# ProPrj_Solid_Cell__2026-03-29.net
KiCad netlist of a schematic drawn in EasyEDA Pro
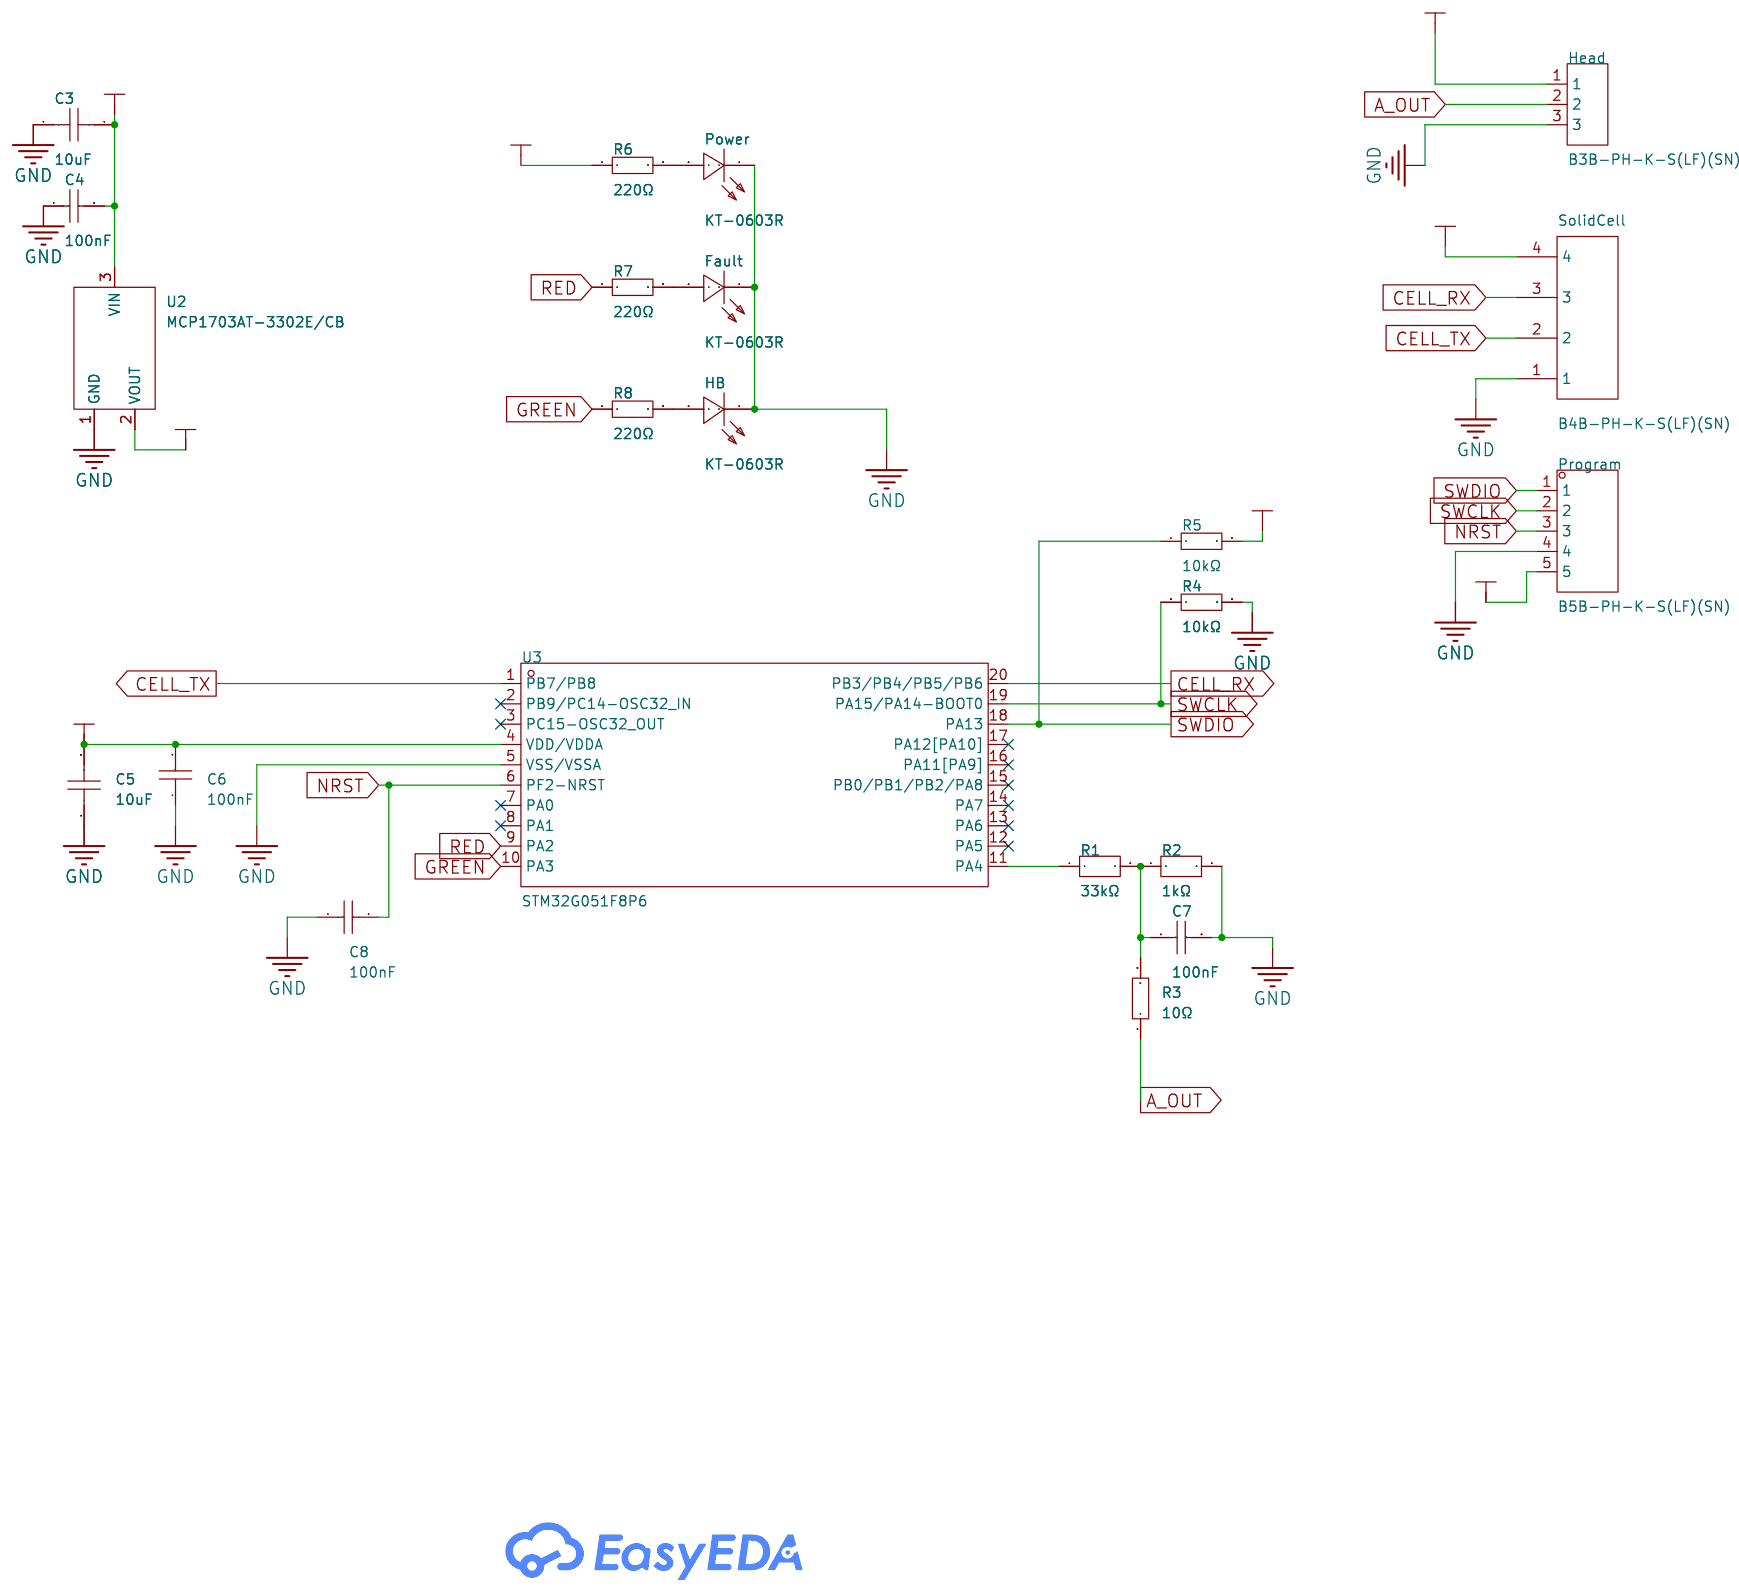
[diagram p0: schematic sheet]

(export (version "E")
  (design (tool "Eeschema 10.0.6"))
  (components
    (comp (ref "C3")
      (value "10uF")
      (footprint "easyedapro:C0603")
      (description "Capacitance:10uF Tolerance:±20% Tolerance:±20% Voltage Rating:25V Temperature Coefficient:X5R")
      (fields
        (field (name "Manufacturer Part") "CL10A106MA8NRNC")
        (field (name "Manufacturer") "SAMSUNG(三星)")
      )
      (libsource (lib "easyedapro") (part "CL10A106KP8NNNC"))
    )
    (comp (ref "C4")
      (value "100nF")
      (footprint "easyedapro:C0603")
      (description "Capacitance:100nF Tolerance:±10% Tolerance:±10% Voltage Rating:50V Temperature Coefficient:X7R")
      (fields
        (field (name "Manufacturer Part") "CC0603KRX7R9BB104")
        (field (name "Manufacturer") "YAGEO(国巨)")
      )
      (libsource (lib "easyedapro") (part "CT41G-0603-2X1-50V-0.1μF-K(N)"))
    )
    (comp (ref "C5")
      (value "10uF")
      (footprint "easyedapro:C0603")
      (description "Capacitance:10uF Tolerance:±20% Tolerance:±20% Voltage Rating:25V Temperature Coefficient:X5R")
      (fields
        (field (name "Manufacturer Part") "CL10A106MA8NRNC")
        (field (name "Manufacturer") "SAMSUNG(三星)")
      )
      (libsource (lib "easyedapro") (part "CL10A106KP8NNNC"))
    )
    (comp (ref "C6")
      (value "100nF")
      (footprint "easyedapro:C0603")
      (description "Capacitance:100nF Tolerance:±10% Tolerance:±10% Voltage Rating:50V Temperature Coefficient:X7R")
      (fields
        (field (name "Manufacturer Part") "CC0603KRX7R9BB104")
        (field (name "Manufacturer") "YAGEO(国巨)")
      )
      (libsource (lib "easyedapro") (part "CT41G-0603-2X1-50V-0.1μF-K(N)"))
    )
    (comp (ref "C7")
      (value "100nF")
      (footprint "easyedapro:C0603")
      (description "Capacitance:100nF Tolerance:±10% Tolerance:±10% Voltage Rating:50V Temperature Coefficient:X7R")
      (fields
        (field (name "Manufacturer Part") "CC0603KRX7R9BB104")
        (field (name "Manufacturer") "YAGEO(国巨)")
      )
      (libsource (lib "easyedapro") (part "CT41G-0603-2X1-50V-0.1μF-K(N)"))
    )
    (comp (ref "C8")
      (value "100nF")
      (footprint "easyedapro:C0603")
      (description "Capacitance:100nF Tolerance:±10% Tolerance:±10% Voltage Rating:50V Temperature Coefficient:X7R")
      (fields
        (field (name "Manufacturer Part") "CC0603KRX7R9BB104")
        (field (name "Manufacturer") "YAGEO(国巨)")
      )
      (libsource (lib "easyedapro") (part "CT41G-0603-2X1-50V-0.1μF-K(N)"))
    )
    (comp (ref "Fault")
      (value "KT-0603R")
      (footprint "easyedapro:LED0603-RD")
      (fields (field (name "Manufacturer") "KENTO"))
      (libsource (lib "easyedapro") (part "KT-0603R"))
    )
    (comp (ref "HB")
      (value "KT-0603R")
      (footprint "easyedapro:LED0603-RD")
      (fields (field (name "Manufacturer") "KENTO"))
      (libsource (lib "easyedapro") (part "KT-0603R"))
    )
    (comp (ref "Head")
      (value "B3B-PH-K-S(LF)(SN)")
      (footprint "easyedapro:CONN-TH_B3B-PH-K-S")
      (fields (field (name "Manufacturer") "JST"))
      (libsource (lib "easyedapro") (part "B3B-PH-K-S(LF)(SN)"))
    )
    (comp (ref "Power")
      (value "KT-0603R")
      (footprint "easyedapro:LED0603-RD")
      (fields (field (name "Manufacturer") "KENTO"))
      (libsource (lib "easyedapro") (part "KT-0603R"))
    )
    (comp (ref "Program")
      (value "B5B-PH-K-S(LF)(SN)")
      (footprint "easyedapro:CONN-TH_B5B-PH-K-S-LF-SN")
      (fields (field (name "Manufacturer") "JST"))
      (libsource (lib "easyedapro") (part "B5B-PH-K-S-(LF)(SN)"))
    )
    (comp (ref "R1")
      (value "33kΩ")
      (footprint "easyedapro:R0603")
      (fields
        (field (name "Manufacturer Part") "0603WAF3302T5E")
        (field (name "Manufacturer") "UNI-ROYAL(厚声)")
      )
      (libsource (lib "easyedapro") (part "RT0603BRD0733KL"))
    )
    (comp (ref "R2")
      (value "1kΩ")
      (footprint "easyedapro:R0603")
      (fields
        (field (name "Manufacturer Part") "0603WAF1001T5E")
        (field (name "Manufacturer") "UNI-ROYAL(厚声)")
      )
      (libsource (lib "easyedapro") (part "RT0603BRE071KL"))
    )
    (comp (ref "R3")
      (value "10Ω")
      (footprint "easyedapro:R0603")
      (fields
        (field (name "Manufacturer Part") "0603WAF100JT5E")
        (field (name "Manufacturer") "UNI-ROYAL(厚声)")
      )
      (libsource (lib "easyedapro") (part "RC0603FR-0715RL"))
    )
    (comp (ref "R4")
      (value "10kΩ")
      (footprint "easyedapro:R0603")
      (fields
        (field (name "Manufacturer Part") "0603WAF1002T5E")
        (field (name "Manufacturer") "UNI-ROYAL(厚声)")
      )
      (libsource (lib "easyedapro") (part "RC0603FR-0710KL"))
    )
    (comp (ref "R5")
      (value "10kΩ")
      (footprint "easyedapro:R0603")
      (fields
        (field (name "Manufacturer Part") "0603WAF1002T5E")
        (field (name "Manufacturer") "UNI-ROYAL(厚声)")
      )
      (libsource (lib "easyedapro") (part "RC0603FR-0710KL"))
    )
    (comp (ref "R6")
      (value "220Ω")
      (footprint "easyedapro:R0603")
      (fields
        (field (name "Manufacturer Part") "0603WAF2200T5E")
        (field (name "Manufacturer") "UNI-ROYAL(厚声)")
      )
      (libsource (lib "easyedapro") (part "RC0603FR-07220RL"))
    )
    (comp (ref "R7")
      (value "220Ω")
      (footprint "easyedapro:R0603")
      (fields
        (field (name "Manufacturer Part") "0603WAF2200T5E")
        (field (name "Manufacturer") "UNI-ROYAL(厚声)")
      )
      (libsource (lib "easyedapro") (part "RC0603FR-07220RL"))
    )
    (comp (ref "R8")
      (value "220Ω")
      (footprint "easyedapro:R0603")
      (fields
        (field (name "Manufacturer Part") "0603WAF2200T5E")
        (field (name "Manufacturer") "UNI-ROYAL(厚声)")
      )
      (libsource (lib "easyedapro") (part "RC0603FR-07220RL"))
    )
    (comp (ref "SolidCell")
      (value "B4B-PH-K-S(LF)(SN)")
      (footprint "easyedapro:CONN-TH_B4B-PH-K-S")
      (fields (field (name "Manufacturer") "JST"))
      (libsource (lib "easyedapro") (part "B4B-PH-K-S(LF)(SN)"))
    )
    (comp (ref "U2")
      (value "MCP1703AT-3302E/CB")
      (footprint "easyedapro:SOT-23-3_L2.9-W1.3-P1.90-LS2.4-BR")
      (fields (field (name "Manufacturer") "MICROCHIP(美国微芯)"))
      (libsource (lib "easyedapro") (part "MCP1703AT-3302E/CB"))
    )
    (comp (ref "U3")
      (value "STM32G051F8P6")
      (footprint "easyedapro:TSSOP-20_L6.5-W4.4-P0.65-LS6.4-BL")
      (fields (field (name "Manufacturer") "ST(意法半导体)"))
      (libsource (lib "easyedapro") (part "STM32G051F8P6"))
    )
  )
  (nets
    (net (code "1") (name "+3V3") (class "Default")
      (node (ref "C5") (pin "2") (pinfunction "2_2") (pintype "unspecified"))
      (node (ref "C6") (pin "2") (pinfunction "2_2") (pintype "input"))
      (node (ref "Program") (pin "5") (pinfunction "5_5") (pintype "unspecified"))
      (node (ref "R5") (pin "2") (pinfunction "2_2") (pintype "input"))
      (node (ref "R6") (pin "1") (pinfunction "1_1") (pintype "input"))
      (node (ref "SolidCell") (pin "4") (pinfunction "4_4") (pintype "input"))
      (node (ref "U2") (pin "2") (pinfunction "VOUT_2") (pintype "unspecified"))
      (node (ref "U3") (pin "4") (pinfunction "VDD/VDDA_4") (pintype "unspecified"))
    )
    (net (code "2") (name "+7.5V") (class "Default")
      (node (ref "C3") (pin "2") (pinfunction "2_2") (pintype "unspecified"))
      (node (ref "C4") (pin "2") (pinfunction "2_2") (pintype "input"))
      (node (ref "Head") (pin "1") (pinfunction "1_1") (pintype "unspecified"))
      (node (ref "U2") (pin "3") (pinfunction "VIN_3") (pintype "unspecified"))
    )
    (net (code "3") (name "A_OUT") (class "Default")
      (node (ref "Head") (pin "2") (pinfunction "2_2") (pintype "unspecified"))
      (node (ref "R3") (pin "1") (pinfunction "1_1") (pintype "input"))
    )
    (net (code "4") (name "CELL_RX") (class "Default")
      (node (ref "SolidCell") (pin "3") (pinfunction "3_3") (pintype "input"))
      (node (ref "U3") (pin "20") (pinfunction "PB3/PB4/PB5/PB6_20") (pintype "unspecified"))
    )
    (net (code "5") (name "CELL_TX") (class "Default")
      (node (ref "SolidCell") (pin "2") (pinfunction "2_2") (pintype "input"))
      (node (ref "U3") (pin "1") (pinfunction "PB7/PB8_1") (pintype "unspecified"))
    )
    (net (code "6") (name "GND") (class "Default")
      (node (ref "C3") (pin "1") (pinfunction "1_1") (pintype "unspecified"))
      (node (ref "C4") (pin "1") (pinfunction "1_1") (pintype "input"))
      (node (ref "C5") (pin "1") (pinfunction "1_1") (pintype "unspecified"))
      (node (ref "C6") (pin "1") (pinfunction "1_1") (pintype "input"))
      (node (ref "C7") (pin "2") (pinfunction "2_2") (pintype "input"))
      (node (ref "C8") (pin "1") (pinfunction "1_1") (pintype "input"))
      (node (ref "Fault") (pin "1") (pinfunction "K_1") (pintype "unspecified"))
      (node (ref "HB") (pin "1") (pinfunction "K_1") (pintype "unspecified"))
      (node (ref "Head") (pin "3") (pinfunction "3_3") (pintype "unspecified"))
      (node (ref "Power") (pin "1") (pinfunction "K_1") (pintype "unspecified"))
      (node (ref "Program") (pin "4") (pinfunction "4_4") (pintype "unspecified"))
      (node (ref "R2") (pin "2") (pinfunction "2_2") (pintype "unspecified"))
      (node (ref "R4") (pin "2") (pinfunction "2_2") (pintype "input"))
      (node (ref "SolidCell") (pin "1") (pinfunction "1_1") (pintype "input"))
      (node (ref "U2") (pin "1") (pinfunction "GND_1") (pintype "unspecified"))
      (node (ref "U3") (pin "5") (pinfunction "VSS/VSSA_5") (pintype "unspecified"))
    )
    (net (code "7") (name "GREEN") (class "Default")
      (node (ref "R8") (pin "1") (pinfunction "1_1") (pintype "input"))
      (node (ref "U3") (pin "10") (pinfunction "PA3_10") (pintype "unspecified"))
    )
    (net (code "8") (name "NRST") (class "Default")
      (node (ref "C8") (pin "2") (pinfunction "2_2") (pintype "input"))
      (node (ref "Program") (pin "3") (pinfunction "3_3") (pintype "unspecified"))
      (node (ref "U3") (pin "6") (pinfunction "PF2-NRST_6") (pintype "unspecified"))
    )
    (net (code "9") (name "Net-(C7-Pad1)") (class "Default")
      (node (ref "C7") (pin "1") (pinfunction "1_1") (pintype "input"))
      (node (ref "R1") (pin "2") (pinfunction "2_2") (pintype "unspecified"))
      (node (ref "R2") (pin "1") (pinfunction "1_1") (pintype "unspecified"))
      (node (ref "R3") (pin "2") (pinfunction "2_2") (pintype "input"))
    )
    (net (code "10") (name "Net-(Fault-A)") (class "Default")
      (node (ref "Fault") (pin "2") (pinfunction "A_2") (pintype "unspecified"))
      (node (ref "R7") (pin "2") (pinfunction "2_2") (pintype "input"))
    )
    (net (code "11") (name "Net-(HB-A)") (class "Default")
      (node (ref "HB") (pin "2") (pinfunction "A_2") (pintype "unspecified"))
      (node (ref "R8") (pin "2") (pinfunction "2_2") (pintype "input"))
    )
    (net (code "12") (name "Net-(Power-A)") (class "Default")
      (node (ref "Power") (pin "2") (pinfunction "A_2") (pintype "unspecified"))
      (node (ref "R6") (pin "2") (pinfunction "2_2") (pintype "input"))
    )
    (net (code "13") (name "Net-(U3-PA4)") (class "Default")
      (node (ref "R1") (pin "1") (pinfunction "1_1") (pintype "unspecified"))
      (node (ref "U3") (pin "11") (pinfunction "PA4_11") (pintype "unspecified"))
    )
    (net (code "14") (name "RED") (class "Default")
      (node (ref "R7") (pin "1") (pinfunction "1_1") (pintype "input"))
      (node (ref "U3") (pin "9") (pinfunction "PA2_9") (pintype "unspecified"))
    )
    (net (code "15") (name "SWCLK") (class "Default")
      (node (ref "Program") (pin "2") (pinfunction "2_2") (pintype "unspecified"))
      (node (ref "R4") (pin "1") (pinfunction "1_1") (pintype "input"))
      (node (ref "U3") (pin "19") (pinfunction "PA15/PA14-BOOT0_19") (pintype "unspecified"))
    )
    (net (code "16") (name "SWDIO") (class "Default")
      (node (ref "Program") (pin "1") (pinfunction "1_1") (pintype "unspecified"))
      (node (ref "R5") (pin "1") (pinfunction "1_1") (pintype "input"))
      (node (ref "U3") (pin "18") (pinfunction "PA13_18") (pintype "unspecified"))
    )
    (net (code "17") (name "unconnected-(U3-PA0-Pad7)") (class "Default")
      (node (ref "U3") (pin "7") (pinfunction "PA0_7") (pintype "unspecified+no_connect"))
    )
    (net (code "18") (name "unconnected-(U3-PA1-Pad8)") (class "Default")
      (node (ref "U3") (pin "8") (pinfunction "PA1_8") (pintype "unspecified+no_connect"))
    )
    (net (code "19") (name "unconnected-(U3-PA5-Pad12)") (class "Default")
      (node (ref "U3") (pin "12") (pinfunction "PA5_12") (pintype "unspecified+no_connect"))
    )
    (net (code "20") (name "unconnected-(U3-PA6-Pad13)") (class "Default")
      (node (ref "U3") (pin "13") (pinfunction "PA6_13") (pintype "unspecified+no_connect"))
    )
    (net (code "21") (name "unconnected-(U3-PA7-Pad14)") (class "Default")
      (node (ref "U3") (pin "14") (pinfunction "PA7_14") (pintype "unspecified+no_connect"))
    )
    (net (code "22") (name "unconnected-(U3-PA11[PA9]-Pad16)") (class "Default")
      (node (ref "U3") (pin "16") (pinfunction "PA11[PA9]_16") (pintype "unspecified+no_connect"))
    )
    (net (code "23") (name "unconnected-(U3-PA12[PA10]-Pad17)") (class "Default")
      (node (ref "U3") (pin "17") (pinfunction "PA12[PA10]_17") (pintype "unspecified+no_connect"))
    )
    (net (code "24") (name "unconnected-(U3-PB0{slash}PB1{slash}PB2{slash}PA8-Pad15)") (class "Default")
      (node (ref "U3") (pin "15") (pinfunction "PB0/PB1/PB2/PA8_15") (pintype "unspecified+no_connect"))
    )
    (net (code "25") (name "unconnected-(U3-PB9{slash}PC14-OSC32_IN-Pad2)") (class "Default")
      (node (ref "U3") (pin "2") (pinfunction "PB9/PC14-OSC32_IN_2") (pintype "unspecified+no_connect"))
    )
    (net (code "26") (name "unconnected-(U3-PC15-OSC32_OUT-Pad3)") (class "Default")
      (node (ref "U3") (pin "3") (pinfunction "PC15-OSC32_OUT_3") (pintype "unspecified+no_connect"))
    )
  )
)
